# FT2232HL_OUT.net
KiCad netlist of a schematic drawn in Altium Designer
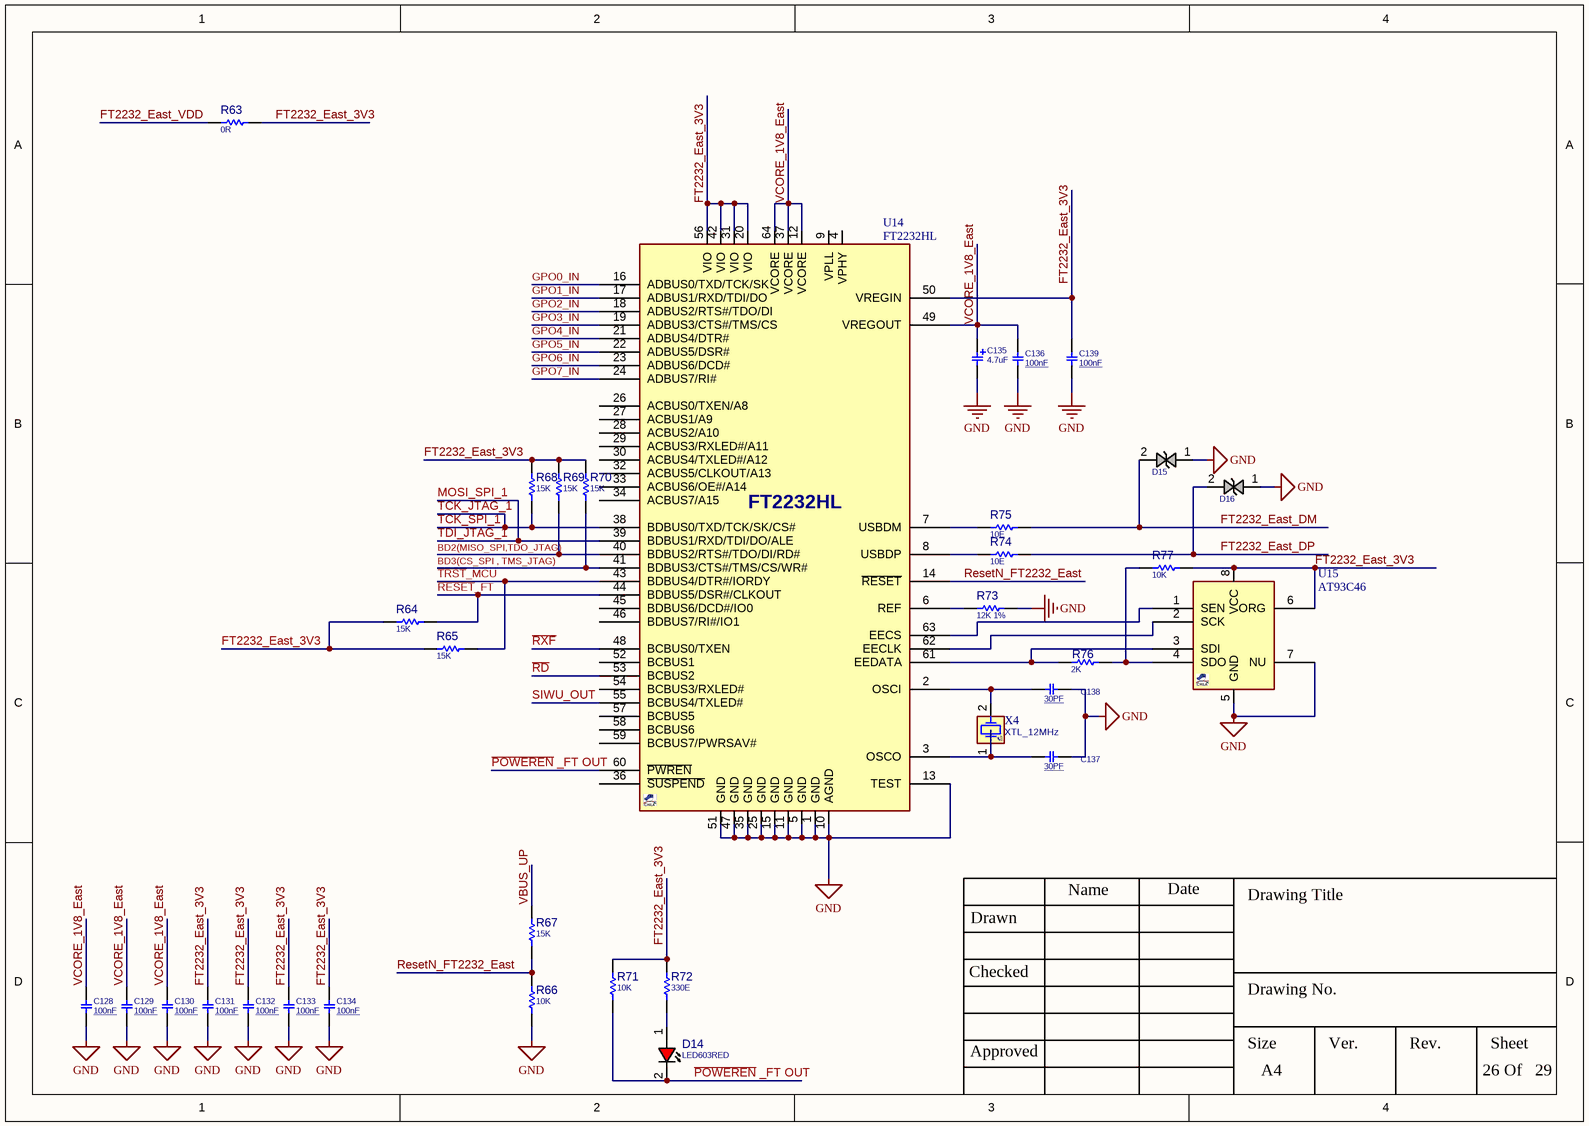
[diagram p0: FT2232HL_OUT.SchDoc]

(export (version "E")
  (design (tool "Eeschema 10.0.6"))
  (components
    (comp (ref "C128")
      (value "100nF")
      (footprint "0603")
      (description "CAP, FILM, 1uF, 16V, Acryl, 20%, 1210")
      (fields (field (name "MANF_P#") "ECP-U1C105MA5") (field (name "MANF") "Panasonic"))
      (libsource (lib "cap_film_smd_passive") (part "CAP_SMD_FILM_1u16v_1210"))
    )
    (comp (ref "C129")
      (value "100nF")
      (footprint "0603")
      (description "CAP, FILM, 1uF, 16V, Acryl, 20%, 1210")
      (fields (field (name "MANF_P#") "ECP-U1C105MA5") (field (name "MANF") "Panasonic"))
      (libsource (lib "cap_film_smd_passive") (part "CAP_SMD_FILM_1u16v_1210"))
    )
    (comp (ref "C130")
      (value "100nF")
      (footprint "0603")
      (description "CAP, FILM, 1uF, 16V, Acryl, 20%, 1210")
      (fields (field (name "MANF_P#") "ECP-U1C105MA5") (field (name "MANF") "Panasonic"))
      (libsource (lib "cap_film_smd_passive") (part "CAP_SMD_FILM_1u16v_1210"))
    )
    (comp (ref "C131")
      (value "100nF")
      (footprint "0603")
      (description "CAP, FILM, 1uF, 16V, Acryl, 20%, 1210")
      (fields (field (name "MANF_P#") "ECP-U1C105MA5") (field (name "MANF") "Panasonic"))
      (libsource (lib "cap_film_smd_passive") (part "CAP_SMD_FILM_1u16v_1210"))
    )
    (comp (ref "C132")
      (value "100nF")
      (footprint "0603")
      (description "CAP, FILM, 1uF, 16V, Acryl, 20%, 1210")
      (fields (field (name "MANF_P#") "ECP-U1C105MA5") (field (name "MANF") "Panasonic"))
      (libsource (lib "cap_film_smd_passive") (part "CAP_SMD_FILM_1u16v_1210"))
    )
    (comp (ref "C133")
      (value "100nF")
      (footprint "0603")
      (description "CAP, FILM, 1uF, 16V, Acryl, 20%, 1210")
      (fields (field (name "MANF_P#") "ECP-U1C105MA5") (field (name "MANF") "Panasonic"))
      (libsource (lib "cap_film_smd_passive") (part "CAP_SMD_FILM_1u16v_1210"))
    )
    (comp (ref "C134")
      (value "100nF")
      (footprint "0603")
      (description "CAP, FILM, 1uF, 16V, Acryl, 20%, 1210")
      (fields (field (name "MANF_P#") "ECP-U1C105MA5") (field (name "MANF") "Panasonic"))
      (libsource (lib "cap_film_smd_passive") (part "CAP_SMD_FILM_1u16v_1210"))
    )
    (comp (ref "C135")
      (value "4.7uF")
      (footprint "C_TN_3216")
      (description "CAP, SMD, TAN")
      (fields (field (name "MANF") "VISHAY") (field (name "MANF_P#") "T55A106M6R3C0300"))
      (libsource (lib "CapTantal_passive") (part "CAP_SMD_TAN_10uF_6.3V"))
    )
    (comp (ref "C136")
      (value "100nF")
      (footprint "0603")
      (description "CAP, FILM, 1uF, 16V, Acryl, 20%, 1210")
      (fields (field (name "MANF_P#") "ECP-U1C105MA5") (field (name "MANF") "Panasonic"))
      (libsource (lib "cap_film_smd_passive") (part "CAP_SMD_FILM_1u16v_1210"))
    )
    (comp (ref "C137")
      (value "30PF")
      (footprint "C0805")
      (description "CAP, MLCC, 1nF, 50V, C0G, 10%, 0402")
      (fields (field (name "MANF") "Murata"))
      (libsource (lib "mlcc_smd_passive") (part "CAP_SMD_MLCC"))
    )
    (comp (ref "C138")
      (value "30PF")
      (footprint "C0805")
      (description "CAP, MLCC, 1nF, 50V, C0G, 10%, 0402")
      (fields (field (name "MANF") "Murata"))
      (libsource (lib "mlcc_smd_passive") (part "CAP_SMD_MLCC"))
    )
    (comp (ref "C139")
      (value "100nF")
      (footprint "0603")
      (description "CAP, FILM, 1uF, 16V, Acryl, 20%, 1210")
      (fields (field (name "MANF_P#") "ECP-U1C105MA5") (field (name "MANF") "Panasonic"))
      (libsource (lib "cap_film_smd_passive") (part "CAP_SMD_FILM_1u16v_1210"))
    )
    (comp (ref "D14")
      (value "LED603RED")
      (footprint "LED0603RED")
      (description "LED, SMD, 0603, RED")
      (fields (field (name "MANF") "MANF") (field (name "MANF_P#") "MANF_PART#"))
      (libsource (lib "led(diode)") (part "LED_SMD_0603_RED"))
    )
    (comp (ref "D15")
      (value "TVS603")
      (footprint "D0603")
      (description "TVS, ESD PROTECT, 24VDC, Bidirectional")
      (fields (field (name "MANF_P#") "PGB0010603MR") (field (name "MANF") "LittelFuse"))
      (libsource (lib "protect_tvs_esd_fuse") (part "TVS_PGB0010603MR"))
    )
    (comp (ref "D16")
      (value "TVS603")
      (footprint "D0603")
      (description "TVS, ESD PROTECT, 24VDC, Bidirectional")
      (fields (field (name "MANF_P#") "PGB0010603MR") (field (name "MANF") "LittelFuse"))
      (libsource (lib "protect_tvs_esd_fuse") (part "TVS_PGB0010603MR"))
    )
    (comp (ref "R63")
      (value "0R")
      (footprint "R0603")
      (description "RESISTOR, SMD")
      (libsource (lib "passive_smd") (part "RES_SMD_0603"))
    )
    (comp (ref "R64")
      (value "15K")
      (footprint "R0603")
      (description "RESISTOR, SMD")
      (libsource (lib "passive_smd") (part "RES_SMD_0603"))
    )
    (comp (ref "R65")
      (value "15K")
      (footprint "R0603")
      (description "RESISTOR, SMD")
      (libsource (lib "passive_smd") (part "RES_SMD_0603"))
    )
    (comp (ref "R66")
      (value "10K")
      (footprint "R0603")
      (description "RESISTOR, SMD")
      (libsource (lib "passive_smd") (part "RES_SMD_0603"))
    )
    (comp (ref "R67")
      (value "15K")
      (footprint "R0603")
      (description "RESISTOR, SMD")
      (libsource (lib "passive_smd") (part "RES_SMD_0603"))
    )
    (comp (ref "R68")
      (value "15K")
      (footprint "R0603")
      (description "RESISTOR, SMD")
      (libsource (lib "passive_smd") (part "RES_SMD_0603"))
    )
    (comp (ref "R69")
      (value "15K")
      (footprint "R0603")
      (description "RESISTOR, SMD")
      (libsource (lib "passive_smd") (part "RES_SMD_0603"))
    )
    (comp (ref "R70")
      (value "15K")
      (footprint "R0603")
      (description "RESISTOR, SMD")
      (libsource (lib "passive_smd") (part "RES_SMD_0603"))
    )
    (comp (ref "R71")
      (value "10K")
      (footprint "R0603")
      (description "RESISTOR, SMD")
      (libsource (lib "passive_smd") (part "RES_SMD_0603"))
    )
    (comp (ref "R72")
      (value "330E")
      (footprint "R0603")
      (description "RESISTOR, SMD")
      (libsource (lib "passive_smd") (part "RES_SMD_0603"))
    )
    (comp (ref "R73")
      (value "12K 1%")
      (footprint "R025W_AX04")
      (description "RESISTOR, THD")
      (fields (field (name "MANF_P#") "RK73H1ETTP4701F") (field (name "MANF") "KOA SPEER"))
      (libsource (lib "passive_thd") (part "RES_THD"))
    )
    (comp (ref "R74")
      (value "10E")
      (footprint "R0603")
      (description "RESISTOR, SMD")
      (libsource (lib "passive_smd") (part "RES_SMD_0603"))
    )
    (comp (ref "R75")
      (value "10E")
      (footprint "R0603")
      (description "RESISTOR, SMD")
      (libsource (lib "passive_smd") (part "RES_SMD_0603"))
    )
    (comp (ref "R76")
      (value "2K")
      (footprint "R025W_AX04")
      (description "RESISTOR, THD")
      (fields (field (name "MANF_P#") "RK73H1ETTP4701F") (field (name "MANF") "KOA SPEER"))
      (libsource (lib "passive_thd") (part "RES_THD"))
    )
    (comp (ref "R77")
      (value "10K")
      (footprint "R025W_AX04")
      (description "RESISTOR, THD")
      (fields (field (name "MANF_P#") "RK73H1ETTP4701F") (field (name "MANF") "KOA SPEER"))
      (libsource (lib "passive_thd") (part "RES_THD"))
    )
    (comp (ref "U14")
      (value "FT2232HL")
      (footprint "QFG50_64")
      (description "USB, DUAL, Multipurpose UART/FIFO, USB High Speed")
      (fields (field (name "MANF") "FTDI"))
      (libsource (lib "usbic") (part "FT2232HL_QFP64"))
    )
    (comp (ref "U15")
      (value "AT93C46")
      (footprint "SO_8")
      (description "EEPROM, SPI, 1KBIT, SOP-8")
      (libsource (lib "memory_eeprom_SPI") (part "EEPROM_SPI_AT93C46_SOP8"))
    )
    (comp (ref "X4")
      (value "XTL_12MHz")
      (footprint "XTL_2_11X5")
      (description "Crystal MOST POPULAR ABL HC49 PACKAGE")
      (fields (field (name "MANF") "ABRACON") (field (name "MANF_P#") "ABLS-8.000MHZ-B4-T"))
      (libsource (lib "crystal") (part "XTL_2_HC49_8MHz_SMD"))
    )
  )
  (nets
    (net (code "2") (name "/BD2(MISO_SPI,TDO_JTAG)") (class "Default")
      (node (ref "R69") (pin "2") (pinfunction "2_2") (pintype "passive"))
      (node (ref "U14") (pin "40") (pinfunction "BDBUS2/RTS#/TDO/DI/RD#_40") (pintype "passive"))
    )
    (net (code "3") (name "/BD3(CS_SPI , TMS_JTAG)") (class "Default")
      (node (ref "R70") (pin "2") (pinfunction "2_2") (pintype "passive"))
      (node (ref "U14") (pin "41") (pinfunction "BDBUS3/CTS#/TMS/CS/WR#_41") (pintype "passive"))
    )
    (net (code "4") (name "/FT2232_East_3V3") (class "Default")
      (node (ref "C131") (pin "1") (pinfunction "1_1") (pintype "passive"))
      (node (ref "C132") (pin "1") (pinfunction "1_1") (pintype "passive"))
      (node (ref "C133") (pin "1") (pinfunction "1_1") (pintype "passive"))
      (node (ref "C134") (pin "1") (pinfunction "1_1") (pintype "passive"))
      (node (ref "C139") (pin "1") (pinfunction "1_1") (pintype "passive"))
      (node (ref "R63") (pin "2") (pinfunction "2_2") (pintype "passive"))
      (node (ref "R64") (pin "1") (pinfunction "1_1") (pintype "passive"))
      (node (ref "R65") (pin "1") (pinfunction "1_1") (pintype "passive"))
      (node (ref "R68") (pin "1") (pinfunction "1_1") (pintype "passive"))
      (node (ref "R69") (pin "1") (pinfunction "1_1") (pintype "passive"))
      (node (ref "R70") (pin "1") (pinfunction "1_1") (pintype "passive"))
      (node (ref "R71") (pin "1") (pinfunction "1_1") (pintype "passive"))
      (node (ref "R72") (pin "1") (pinfunction "1_1") (pintype "passive"))
      (node (ref "R77") (pin "1") (pinfunction "1_1") (pintype "passive"))
      (node (ref "U14") (pin "20") (pinfunction "VIO_20") (pintype "passive"))
      (node (ref "U14") (pin "31") (pinfunction "VIO_31") (pintype "passive"))
      (node (ref "U14") (pin "42") (pinfunction "VIO_42") (pintype "passive"))
      (node (ref "U14") (pin "50") (pinfunction "VREGIN_50") (pintype "passive"))
      (node (ref "U14") (pin "56") (pinfunction "VIO_56") (pintype "passive"))
      (node (ref "U15") (pin "6") (pinfunction "ORG_6") (pintype "passive"))
      (node (ref "U15") (pin "8") (pinfunction "VCC_8") (pintype "passive"))
    )
    (net (code "5") (name "/FT2232_East_DM") (class "Default")
      (node (ref "D15") (pin "2") (pinfunction "2_2") (pintype "passive"))
      (node (ref "R75") (pin "1") (pinfunction "1_1") (pintype "passive"))
    )
    (net (code "6") (name "/FT2232_East_DP") (class "Default")
      (node (ref "D16") (pin "2") (pinfunction "2_2") (pintype "passive"))
      (node (ref "R74") (pin "1") (pinfunction "1_1") (pintype "passive"))
    )
    (net (code "7") (name "/FT2232_East_VDD") (class "Default")
      (node (ref "R63") (pin "1") (pinfunction "1_1") (pintype "passive"))
    )
    (net (code "8") (name "/GPO0_IN") (class "Default")
      (node (ref "U14") (pin "16") (pinfunction "ADBUS0/TXD/TCK/SK_16") (pintype "passive"))
    )
    (net (code "9") (name "/GPO1_IN") (class "Default")
      (node (ref "U14") (pin "17") (pinfunction "ADBUS1/RXD/TDI/DO_17") (pintype "passive"))
    )
    (net (code "10") (name "/GPO2_IN") (class "Default")
      (node (ref "U14") (pin "18") (pinfunction "ADBUS2/RTS#/TDO/DI_18") (pintype "passive"))
    )
    (net (code "11") (name "/GPO3_IN") (class "Default")
      (node (ref "U14") (pin "19") (pinfunction "ADBUS3/CTS#/TMS/CS_19") (pintype "passive"))
    )
    (net (code "12") (name "/GPO4_IN") (class "Default")
      (node (ref "U14") (pin "21") (pinfunction "ADBUS4/DTR#_21") (pintype "passive"))
    )
    (net (code "13") (name "/GPO5_IN") (class "Default")
      (node (ref "U14") (pin "22") (pinfunction "ADBUS5/DSR#_22") (pintype "passive"))
    )
    (net (code "14") (name "/GPO6_IN") (class "Default")
      (node (ref "U14") (pin "23") (pinfunction "ADBUS6/DCD#_23") (pintype "passive"))
    )
    (net (code "15") (name "/GPO7_IN") (class "Default")
      (node (ref "U14") (pin "24") (pinfunction "ADBUS7/RI#_24") (pintype "passive"))
    )
    (net (code "16") (name "/MOSI_SPI_1") (class "Default")
      (node (ref "U14") (pin "39") (pinfunction "BDBUS1/RXD/TDI/DO/ALE_39") (pintype "passive"))
    )
    (net (code "17") (name "/ResetN_FT2232_East") (class "Default")
      (node (ref "R66") (pin "1") (pinfunction "1_1") (pintype "passive"))
      (node (ref "R67") (pin "2") (pinfunction "2_2") (pintype "passive"))
      (node (ref "U14") (pin "14") (pinfunction "~{RESET}_14") (pintype "passive"))
    )
    (net (code "18") (name "/SIWU_OUT") (class "Default")
      (node (ref "U14") (pin "55") (pinfunction "BCBUS4/TXLED#_55") (pintype "passive"))
    )
    (net (code "19") (name "/TCK_JTAG_1") (class "Default")
      (node (ref "R68") (pin "2") (pinfunction "2_2") (pintype "passive"))
      (node (ref "U14") (pin "38") (pinfunction "BDBUS0/TXD/TCK/SK/CS#_38") (pintype "passive"))
    )
    (net (code "20") (name "/VBUS_UP") (class "Default")
      (node (ref "R67") (pin "1") (pinfunction "1_1") (pintype "passive"))
    )
    (net (code "21") (name "/VCORE_1V8_East") (class "Default")
      (node (ref "C128") (pin "1") (pinfunction "1_1") (pintype "passive"))
      (node (ref "C129") (pin "1") (pinfunction "1_1") (pintype "passive"))
      (node (ref "C130") (pin "1") (pinfunction "1_1") (pintype "passive"))
      (node (ref "C135") (pin "1") (pinfunction "1_1") (pintype "passive"))
      (node (ref "C136") (pin "1") (pinfunction "1_1") (pintype "passive"))
      (node (ref "U14") (pin "12") (pinfunction "VCORE_12") (pintype "passive"))
      (node (ref "U14") (pin "37") (pinfunction "VCORE_37") (pintype "passive"))
      (node (ref "U14") (pin "49") (pinfunction "VREGOUT_49") (pintype "passive"))
      (node (ref "U14") (pin "64") (pinfunction "VCORE_64") (pintype "passive"))
    )
    (net (code "22") (name "/~{POWEREN} _FT OUT") (class "Default")
      (node (ref "D14") (pin "2") (pinfunction "CATHODE_2") (pintype "passive"))
      (node (ref "R71") (pin "2") (pinfunction "2_2") (pintype "passive"))
      (node (ref "U14") (pin "60") (pinfunction "~{PWREN}_60") (pintype "passive"))
    )
    (net (code "23") (name "/~{RD}") (class "Default")
      (node (ref "U14") (pin "53") (pinfunction "BCBUS2_53") (pintype "passive"))
    )
    (net (code "24") (name "/~{RESET}_FT") (class "Default")
      (node (ref "R64") (pin "2") (pinfunction "2_2") (pintype "passive"))
      (node (ref "U14") (pin "44") (pinfunction "BDBUS5/DSR#/CLKOUT_44") (pintype "passive"))
    )
    (net (code "25") (name "/~{RXF}") (class "Default")
      (node (ref "U14") (pin "48") (pinfunction "BCBUS0/TXEN_48") (pintype "passive"))
    )
    (net (code "26") (name "/~{TRST}_MCU") (class "Default")
      (node (ref "R65") (pin "2") (pinfunction "2_2") (pintype "passive"))
      (node (ref "U14") (pin "43") (pinfunction "BDBUS4/DTR#/IORDY_43") (pintype "passive"))
    )
    (net (code "27") (name "GND") (class "Default")
      (node (ref "C128") (pin "2") (pinfunction "2_2") (pintype "passive"))
      (node (ref "C129") (pin "2") (pinfunction "2_2") (pintype "passive"))
      (node (ref "C130") (pin "2") (pinfunction "2_2") (pintype "passive"))
      (node (ref "C131") (pin "2") (pinfunction "2_2") (pintype "passive"))
      (node (ref "C132") (pin "2") (pinfunction "2_2") (pintype "passive"))
      (node (ref "C133") (pin "2") (pinfunction "2_2") (pintype "passive"))
      (node (ref "C134") (pin "2") (pinfunction "2_2") (pintype "passive"))
      (node (ref "C135") (pin "2") (pinfunction "2_2") (pintype "passive"))
      (node (ref "C136") (pin "2") (pinfunction "2_2") (pintype "passive"))
      (node (ref "C137") (pin "2") (pinfunction "2_2") (pintype "passive"))
      (node (ref "C138") (pin "2") (pinfunction "2_2") (pintype "passive"))
      (node (ref "C139") (pin "2") (pinfunction "2_2") (pintype "passive"))
      (node (ref "D15") (pin "1") (pinfunction "1_1") (pintype "passive"))
      (node (ref "D16") (pin "1") (pinfunction "1_1") (pintype "passive"))
      (node (ref "R66") (pin "2") (pinfunction "2_2") (pintype "passive"))
      (node (ref "R73") (pin "1") (pinfunction "1_1") (pintype "passive"))
      (node (ref "U14") (pin "1") (pinfunction "GND_1") (pintype "passive"))
      (node (ref "U14") (pin "10") (pinfunction "AGND_10") (pintype "passive"))
      (node (ref "U14") (pin "11") (pinfunction "GND_11") (pintype "passive"))
      (node (ref "U14") (pin "13") (pinfunction "TEST_13") (pintype "passive"))
      (node (ref "U14") (pin "15") (pinfunction "GND_15") (pintype "passive"))
      (node (ref "U14") (pin "25") (pinfunction "GND_25") (pintype "passive"))
      (node (ref "U14") (pin "35") (pinfunction "GND_35") (pintype "passive"))
      (node (ref "U14") (pin "47") (pinfunction "GND_47") (pintype "passive"))
      (node (ref "U14") (pin "5") (pinfunction "GND_5") (pintype "passive"))
      (node (ref "U14") (pin "51") (pinfunction "GND_51") (pintype "passive"))
      (node (ref "U15") (pin "5") (pinfunction "GND_5") (pintype "passive"))
      (node (ref "U15") (pin "7") (pinfunction "NU_7") (pintype "passive"))
    )
    (net (code "28") (name "Net-(D14-ANODE)") (class "Default")
      (node (ref "D14") (pin "1") (pinfunction "ANODE_1") (pintype "passive"))
      (node (ref "R72") (pin "2") (pinfunction "2_2") (pintype "passive"))
    )
    (net (code "29") (name "Net-(U14-EECLK)") (class "Default")
      (node (ref "U14") (pin "62") (pinfunction "EECLK_62") (pintype "passive"))
      (node (ref "U15") (pin "2") (pinfunction "SCK_2") (pintype "passive"))
    )
    (net (code "30") (name "Net-(U14-EECS)") (class "Default")
      (node (ref "U14") (pin "63") (pinfunction "EECS_63") (pintype "passive"))
      (node (ref "U15") (pin "1") (pinfunction "SEN_1") (pintype "passive"))
    )
    (net (code "31") (name "Net-(U14-EEDATA)") (class "Default")
      (node (ref "R76") (pin "2") (pinfunction "2_2") (pintype "passive"))
      (node (ref "U14") (pin "61") (pinfunction "EEDATA_61") (pintype "passive"))
      (node (ref "U15") (pin "3") (pinfunction "SDI_3") (pintype "passive"))
    )
    (net (code "32") (name "Net-(U14-OSCI)") (class "Default")
      (node (ref "C138") (pin "1") (pinfunction "1_1") (pintype "passive"))
      (node (ref "U14") (pin "2") (pinfunction "OSCI_2") (pintype "passive"))
      (node (ref "X4") (pin "2") (pinfunction "OSC2_2") (pintype "passive"))
    )
    (net (code "33") (name "Net-(U14-OSCO)") (class "Default")
      (node (ref "C137") (pin "1") (pinfunction "1_1") (pintype "passive"))
      (node (ref "U14") (pin "3") (pinfunction "OSCO_3") (pintype "passive"))
      (node (ref "X4") (pin "1") (pinfunction "OSC1_1") (pintype "passive"))
    )
    (net (code "34") (name "Net-(U14-REF)") (class "Default")
      (node (ref "R73") (pin "2") (pinfunction "2_2") (pintype "passive"))
      (node (ref "U14") (pin "6") (pinfunction "REF_6") (pintype "passive"))
    )
    (net (code "35") (name "Net-(U14-USBDM)") (class "Default")
      (node (ref "R75") (pin "2") (pinfunction "2_2") (pintype "passive"))
      (node (ref "U14") (pin "7") (pinfunction "USBDM_7") (pintype "passive"))
    )
    (net (code "36") (name "Net-(U14-USBDP)") (class "Default")
      (node (ref "R74") (pin "2") (pinfunction "2_2") (pintype "passive"))
      (node (ref "U14") (pin "8") (pinfunction "USBDP_8") (pintype "passive"))
    )
    (net (code "37") (name "Net-(U15-SDO)") (class "Default")
      (node (ref "R76") (pin "1") (pinfunction "1_1") (pintype "passive"))
      (node (ref "R77") (pin "2") (pinfunction "2_2") (pintype "passive"))
      (node (ref "U15") (pin "4") (pinfunction "SDO_4") (pintype "passive"))
    )
    (net (code "38") (name "unconnected-(U14-ACBUS0{slash}TXEN{slash}A8-Pad26)") (class "Default")
      (node (ref "U14") (pin "26") (pinfunction "ACBUS0/TXEN/A8_26") (pintype "passive"))
    )
    (net (code "39") (name "unconnected-(U14-ACBUS1{slash}A9-Pad27)") (class "Default")
      (node (ref "U14") (pin "27") (pinfunction "ACBUS1/A9_27") (pintype "passive"))
    )
    (net (code "40") (name "unconnected-(U14-ACBUS2{slash}A10-Pad28)") (class "Default")
      (node (ref "U14") (pin "28") (pinfunction "ACBUS2/A10_28") (pintype "passive"))
    )
    (net (code "41") (name "unconnected-(U14-ACBUS3{slash}RXLED#{slash}A11-Pad29)") (class "Default")
      (node (ref "U14") (pin "29") (pinfunction "ACBUS3/RXLED#/A11_29") (pintype "passive"))
    )
    (net (code "42") (name "unconnected-(U14-ACBUS4{slash}TXLED#{slash}A12-Pad30)") (class "Default")
      (node (ref "U14") (pin "30") (pinfunction "ACBUS4/TXLED#/A12_30") (pintype "passive"))
    )
    (net (code "43") (name "unconnected-(U14-ACBUS5{slash}CLKOUT{slash}A13-Pad32)") (class "Default")
      (node (ref "U14") (pin "32") (pinfunction "ACBUS5/CLKOUT/A13_32") (pintype "passive"))
    )
    (net (code "44") (name "unconnected-(U14-ACBUS6{slash}OE#{slash}A14-Pad33)") (class "Default")
      (node (ref "U14") (pin "33") (pinfunction "ACBUS6/OE#/A14_33") (pintype "passive"))
    )
    (net (code "45") (name "unconnected-(U14-ACBUS7{slash}A15-Pad34)") (class "Default")
      (node (ref "U14") (pin "34") (pinfunction "ACBUS7/A15_34") (pintype "passive"))
    )
    (net (code "46") (name "unconnected-(U14-BCBUS1-Pad52)") (class "Default")
      (node (ref "U14") (pin "52") (pinfunction "BCBUS1_52") (pintype "passive"))
    )
    (net (code "47") (name "unconnected-(U14-BCBUS3{slash}RXLED#-Pad54)") (class "Default")
      (node (ref "U14") (pin "54") (pinfunction "BCBUS3/RXLED#_54") (pintype "passive"))
    )
    (net (code "48") (name "unconnected-(U14-BCBUS5-Pad57)") (class "Default")
      (node (ref "U14") (pin "57") (pinfunction "BCBUS5_57") (pintype "passive"))
    )
    (net (code "49") (name "unconnected-(U14-BCBUS6-Pad58)") (class "Default")
      (node (ref "U14") (pin "58") (pinfunction "BCBUS6_58") (pintype "passive"))
    )
    (net (code "50") (name "unconnected-(U14-BCBUS7{slash}PWRSAV#-Pad59)") (class "Default")
      (node (ref "U14") (pin "59") (pinfunction "BCBUS7/PWRSAV#_59") (pintype "passive"))
    )
    (net (code "51") (name "unconnected-(U14-BDBUS6{slash}DCD#{slash}IO0-Pad45)") (class "Default")
      (node (ref "U14") (pin "45") (pinfunction "BDBUS6/DCD#/IO0_45") (pintype "passive"))
    )
    (net (code "52") (name "unconnected-(U14-BDBUS7{slash}RI#{slash}IO1-Pad46)") (class "Default")
      (node (ref "U14") (pin "46") (pinfunction "BDBUS7/RI#/IO1_46") (pintype "passive"))
    )
    (net (code "53") (name "unconnected-(U14-VPHY-Pad4)") (class "Default")
      (node (ref "U14") (pin "4") (pinfunction "VPHY_4") (pintype "passive"))
    )
    (net (code "54") (name "unconnected-(U14-VPLL-Pad9)") (class "Default")
      (node (ref "U14") (pin "9") (pinfunction "VPLL_9") (pintype "passive"))
    )
    (net (code "55") (name "unconnected-(U14-~{SUSPEND}-Pad36)") (class "Default")
      (node (ref "U14") (pin "36") (pinfunction "~{SUSPEND}_36") (pintype "passive"))
    )
  )
)
